# ADXL_eth_con.net
KiCad netlist of a schematic drawn in EAGLE
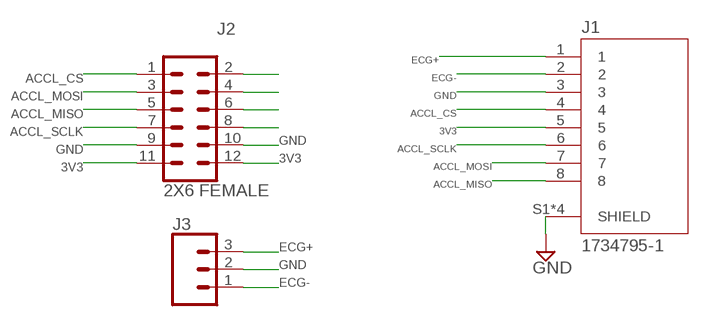
[diagram p0: schematic, sheet 1]

(export (version "E")
  (design (tool "Eeschema 10.0.6"))
  (components
    (comp (ref "J1")
      (value "1734795-1")
      (footprint "eagle-import:TE_1734795-1")
      (fields (field (name "MF") "TE Connectivity"))
      (libsource (lib "eagle-import") (part "1734795-1"))
    )
    (comp (ref "J2")
      (value "2X6 FEMALE")
      (footprint "eagle-import:2X6")
      (libsource (lib "eagle-import") (part "CONN_06X2PTH_FEMALE"))
    )
    (comp (ref "J3")
      (value "CONN_03")
      (footprint "eagle-import:1X03")
      (libsource (lib "eagle-import") (part "CONN_03"))
    )
  )
  (nets
    (net (code "1") (name "3V3") (class "Default")
      (node (ref "J1") (pin "5") (pinfunction "5_5") (pintype "passive"))
      (node (ref "J2") (pin "11") (pinfunction "11_11") (pintype "passive"))
      (node (ref "J2") (pin "12") (pinfunction "12_12") (pintype "passive"))
    )
    (net (code "2") (name "ACCL_CS") (class "Default")
      (node (ref "J1") (pin "4") (pinfunction "4_4") (pintype "passive"))
      (node (ref "J2") (pin "1") (pinfunction "1_1") (pintype "passive"))
    )
    (net (code "3") (name "ACCL_MISO") (class "Default")
      (node (ref "J1") (pin "8") (pinfunction "8_8") (pintype "passive"))
      (node (ref "J2") (pin "5") (pinfunction "5_5") (pintype "passive"))
    )
    (net (code "4") (name "ACCL_MOSI") (class "Default")
      (node (ref "J1") (pin "7") (pinfunction "7_7") (pintype "passive"))
      (node (ref "J2") (pin "3") (pinfunction "3_3") (pintype "passive"))
    )
    (net (code "5") (name "ACCL_SCLK") (class "Default")
      (node (ref "J1") (pin "6") (pinfunction "6_6") (pintype "passive"))
      (node (ref "J2") (pin "7") (pinfunction "7_7") (pintype "passive"))
    )
    (net (code "6") (name "ECG+") (class "Default")
      (node (ref "J1") (pin "1") (pinfunction "1_1") (pintype "passive"))
      (node (ref "J3") (pin "3") (pinfunction "3_3") (pintype "passive"))
    )
    (net (code "7") (name "ECG-") (class "Default")
      (node (ref "J1") (pin "2") (pinfunction "2_2") (pintype "passive"))
      (node (ref "J3") (pin "1") (pinfunction "1_1") (pintype "passive"))
    )
    (net (code "8") (name "GND") (class "Default")
      (node (ref "J1") (pin "3") (pinfunction "3_3") (pintype "passive"))
      (node (ref "J1") (pin "S1") (pinfunction "SHIELD_S1") (pintype "passive"))
      (node (ref "J1") (pin "S2") (pinfunction "SHIELD_S2") (pintype "passive"))
      (node (ref "J1") (pin "S3") (pinfunction "SHIELD_S3") (pintype "passive"))
      (node (ref "J1") (pin "S4") (pinfunction "SHIELD_S4") (pintype "passive"))
      (node (ref "J2") (pin "10") (pinfunction "10_10") (pintype "passive"))
      (node (ref "J2") (pin "9") (pinfunction "9_9") (pintype "passive"))
      (node (ref "J3") (pin "2") (pinfunction "2_2") (pintype "passive"))
    )
    (net (code "9") (name "unconnected-(J2-Pad2)") (class "Default")
      (node (ref "J2") (pin "2") (pinfunction "2_2") (pintype "passive"))
    )
    (net (code "10") (name "unconnected-(J2-Pad4)") (class "Default")
      (node (ref "J2") (pin "4") (pinfunction "4_4") (pintype "passive"))
    )
    (net (code "11") (name "unconnected-(J2-Pad6)") (class "Default")
      (node (ref "J2") (pin "6") (pinfunction "6_6") (pintype "passive"))
    )
    (net (code "12") (name "unconnected-(J2-Pad8)") (class "Default")
      (node (ref "J2") (pin "8") (pinfunction "8_8") (pintype "passive"))
    )
  )
)
